# MCU.net
KiCad netlist of a schematic drawn in Altium Designer
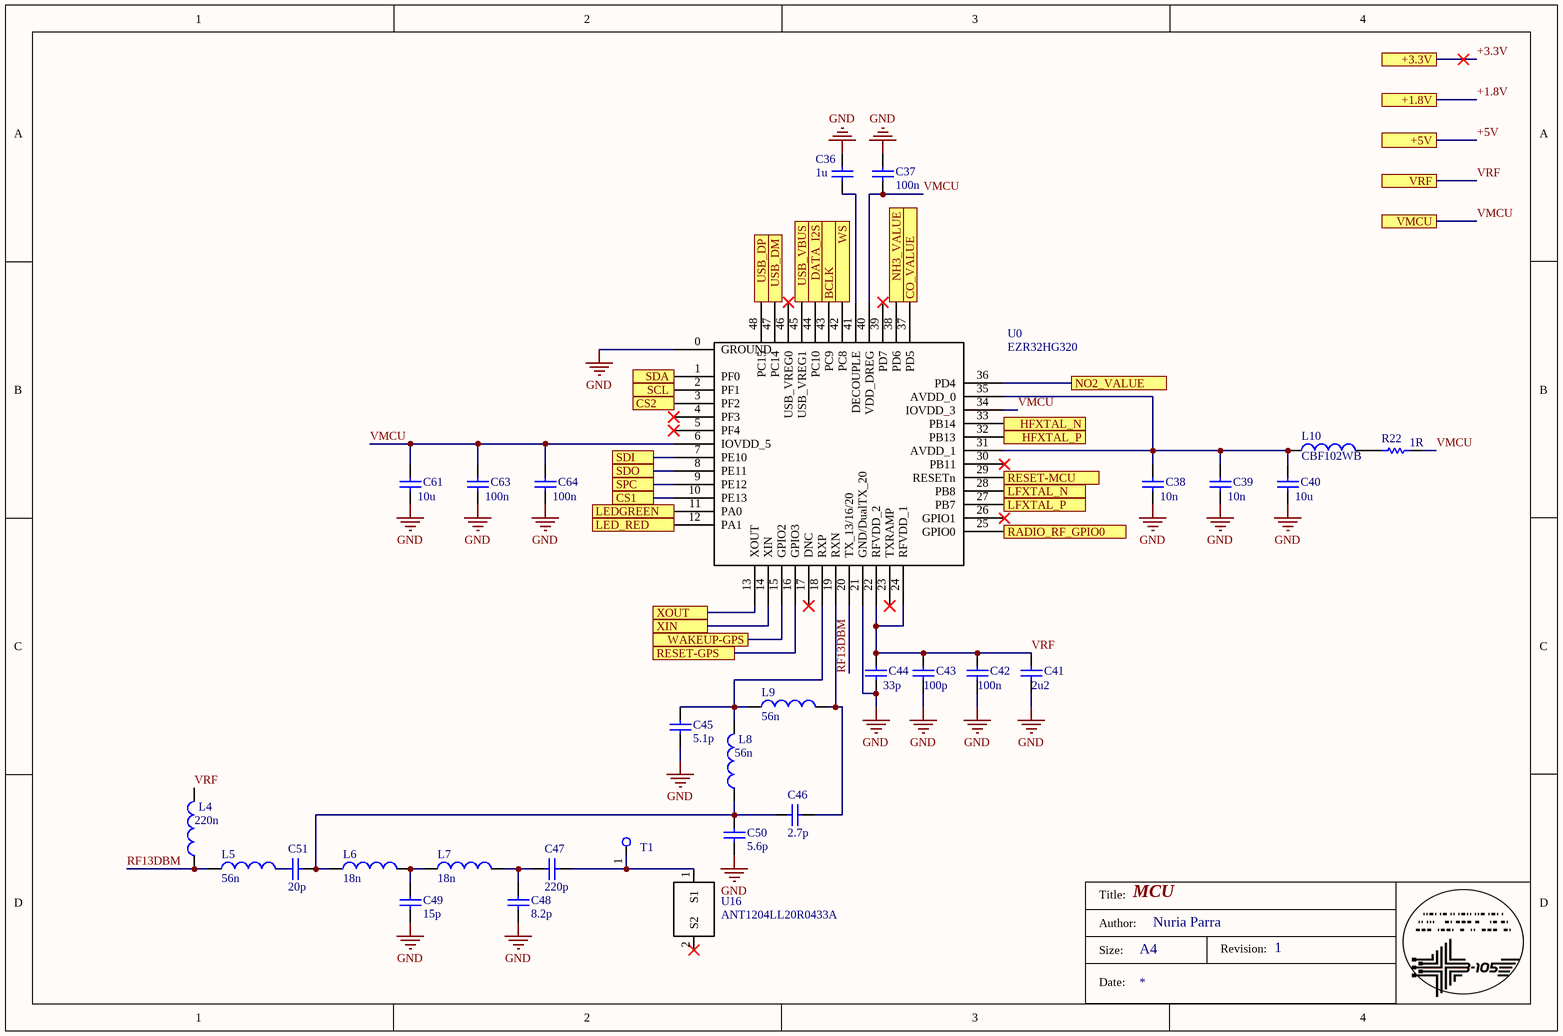
[diagram p0: MCU.SchDoc]

(export (version "E")
  (design (tool "Eeschema 10.0.6"))
  (components
    (comp (ref "C36")
      (value "1u")
      (footprint "0603 Cap")
      (fields (field (name "Comment") "Cap"))
      (libsource (lib "B105rlc") (part "Cap"))
    )
    (comp (ref "C37")
      (value "100n")
      (footprint "0603 Cap")
      (fields (field (name "Comment") "Cap"))
      (libsource (lib "B105rlc") (part "Cap"))
    )
    (comp (ref "C38")
      (value "10n")
      (footprint "0603 Cap")
      (fields (field (name "Comment") "Cap"))
      (libsource (lib "B105rlc") (part "Cap"))
    )
    (comp (ref "C39")
      (value "10n")
      (footprint "0603 Cap")
      (fields (field (name "Comment") "Cap"))
      (libsource (lib "B105rlc") (part "Cap"))
    )
    (comp (ref "C40")
      (value "10u")
      (footprint "0603 Cap")
      (fields (field (name "Comment") "Cap"))
      (libsource (lib "B105rlc") (part "Cap"))
    )
    (comp (ref "C41")
      (value "2u2")
      (footprint "0603 Cap")
      (fields (field (name "Comment") "Cap"))
      (libsource (lib "B105rlc") (part "Cap"))
    )
    (comp (ref "C42")
      (value "100n")
      (footprint "0603 Cap")
      (fields (field (name "Comment") "Cap"))
      (libsource (lib "B105rlc") (part "Cap"))
    )
    (comp (ref "C43")
      (value "100p")
      (footprint "0603 Cap")
      (fields (field (name "Comment") "Cap"))
      (libsource (lib "B105rlc") (part "Cap"))
    )
    (comp (ref "C44")
      (value "33p")
      (footprint "0603 Cap")
      (fields (field (name "Comment") "Cap"))
      (libsource (lib "B105rlc") (part "Cap"))
    )
    (comp (ref "C45")
      (value "5.1p")
      (footprint "0603 Cap")
      (fields (field (name "Comment") "Cap"))
      (libsource (lib "B105rlc") (part "Cap"))
    )
    (comp (ref "C46")
      (value "2.7p")
      (footprint "0603 Cap")
      (fields (field (name "Comment") "Cap"))
      (libsource (lib "B105rlc") (part "Cap"))
    )
    (comp (ref "C47")
      (value "220p")
      (footprint "0603 Cap")
      (fields (field (name "Comment") "Cap"))
      (libsource (lib "B105rlc") (part "Cap"))
    )
    (comp (ref "C48")
      (value "8.2p")
      (footprint "0603 Cap")
      (fields (field (name "Comment") "Cap"))
      (libsource (lib "B105rlc") (part "Cap"))
    )
    (comp (ref "C49")
      (value "15p")
      (footprint "0603 Cap")
      (fields (field (name "Comment") "Cap"))
      (libsource (lib "B105rlc") (part "Cap"))
    )
    (comp (ref "C50")
      (value "5.6p")
      (footprint "0603 Cap")
      (fields (field (name "Comment") "Cap"))
      (libsource (lib "B105rlc") (part "Cap"))
    )
    (comp (ref "C51")
      (value "20p")
      (footprint "0603 Cap")
      (fields (field (name "Comment") "Cap"))
      (libsource (lib "B105rlc") (part "Cap"))
    )
    (comp (ref "C61")
      (value "10u")
      (footprint "0603 Cap")
      (fields (field (name "Comment") "Cap"))
      (libsource (lib "B105rlc") (part "Cap"))
    )
    (comp (ref "C63")
      (value "100n")
      (footprint "0603 Cap")
      (fields (field (name "Comment") "Cap"))
      (libsource (lib "B105rlc") (part "Cap"))
    )
    (comp (ref "C64")
      (value "100n")
      (footprint "0603 Cap")
      (fields (field (name "Comment") "Cap"))
      (libsource (lib "B105rlc") (part "Cap"))
    )
    (comp (ref "L4")
      (value "220n")
      (footprint "0603 IND")
      (fields (field (name "Comment") "L?"))
      (libsource (lib "B105rlc") (part "Ind"))
    )
    (comp (ref "L5")
      (value "56n")
      (footprint "0603 IND")
      (fields (field (name "Comment") "L?"))
      (libsource (lib "B105rlc") (part "Ind"))
    )
    (comp (ref "L6")
      (value "18n")
      (footprint "0603 IND")
      (fields (field (name "Comment") "L?"))
      (libsource (lib "B105rlc") (part "Ind"))
    )
    (comp (ref "L7")
      (value "18n")
      (footprint "0603 IND")
      (fields (field (name "Comment") "L?"))
      (libsource (lib "B105rlc") (part "Ind"))
    )
    (comp (ref "L8")
      (value "56n")
      (footprint "0603 IND")
      (fields (field (name "Comment") "L?"))
      (libsource (lib "B105rlc") (part "Ind"))
    )
    (comp (ref "L9")
      (value "56n")
      (footprint "0603 IND")
      (fields (field (name "Comment") "L?"))
      (libsource (lib "B105rlc") (part "Ind"))
    )
    (comp (ref "L10")
      (value "CBF102WB")
      (footprint "0603 IND")
      (fields (field (name "Comment") "L?"))
      (libsource (lib "B105rlc") (part "Ind"))
    )
    (comp (ref "R22")
      (value "1R")
      (footprint "0603 Res")
      (fields (field (name "Comment") "Res"))
      (libsource (lib "B105rlc") (part "Res"))
    )
    (comp (ref "T1")
      (value "testpoint")
      (footprint "testpoint")
      (libsource (lib "Libreria Nuria") (part "testpoint"))
    )
    (comp (ref "U0")
      (value "EZR32HG320")
      (footprint "EZ32HG")
      (libsource (lib "Libreria Nuria") (part "EZR32HG320"))
    )
    (comp (ref "U16")
      (value "ANT1204LL20R0433A")
      (footprint "ANT1204LL20R0433A")
      (libsource (lib "Libreria Nuria") (part "ANT1204LL20R0433A"))
    )
  )
  (nets
    (net (code "4") (name "/BCLK") (class "Default")
      (node (ref "U0") (pin "43") (pinfunction "PC9_43") (pintype "passive"))
    )
    (net (code "5") (name "/CO_VALUE") (class "Default")
      (node (ref "U0") (pin "37") (pinfunction "PD5_37") (pintype "passive"))
    )
    (net (code "6") (name "/CS1") (class "Default")
      (node (ref "U0") (pin "10") (pinfunction "PE13_10") (pintype "passive"))
    )
    (net (code "7") (name "/CS2") (class "Default")
      (node (ref "U0") (pin "3") (pinfunction "PF2_3") (pintype "passive"))
    )
    (net (code "8") (name "/DATA_I2S") (class "Default")
      (node (ref "U0") (pin "44") (pinfunction "PC10_44") (pintype "passive"))
    )
    (net (code "9") (name "/HFXTAL_N") (class "Default")
      (node (ref "U0") (pin "33") (pinfunction "PB14_33") (pintype "passive"))
    )
    (net (code "10") (name "/HFXTAL_P") (class "Default")
      (node (ref "U0") (pin "32") (pinfunction "PB13_32") (pintype "passive"))
    )
    (net (code "11") (name "/LEDGREEN") (class "Default")
      (node (ref "U0") (pin "11") (pinfunction "PA0_11") (pintype "passive"))
    )
    (net (code "12") (name "/LED_RED") (class "Default")
      (node (ref "U0") (pin "12") (pinfunction "PA1_12") (pintype "passive"))
    )
    (net (code "13") (name "/LFXTAL_N") (class "Default")
      (node (ref "U0") (pin "28") (pinfunction "PB8_28") (pintype "passive"))
    )
    (net (code "14") (name "/LFXTAL_P") (class "Default")
      (node (ref "U0") (pin "27") (pinfunction "PB7_27") (pintype "passive"))
    )
    (net (code "15") (name "/NH3_VALUE") (class "Default")
      (node (ref "U0") (pin "38") (pinfunction "PD6_38") (pintype "passive"))
    )
    (net (code "16") (name "/NO2_VALUE") (class "Default")
      (node (ref "U0") (pin "36") (pinfunction "PD4_36") (pintype "passive"))
    )
    (net (code "17") (name "/RADIO_RF_GPIO0") (class "Default")
      (node (ref "U0") (pin "25") (pinfunction "GPIO0_25") (pintype "passive"))
    )
    (net (code "18") (name "/RESET-GPS") (class "Default")
      (node (ref "U0") (pin "16") (pinfunction "GPIO3_16") (pintype "passive"))
    )
    (net (code "19") (name "/RESET-MCU") (class "Default")
      (node (ref "U0") (pin "29") (pinfunction "RESETn_29") (pintype "passive"))
    )
    (net (code "20") (name "/RF13DBM") (class "Default")
      (node (ref "L4") (pin "1") (pinfunction "1_1") (pintype "passive"))
      (node (ref "L5") (pin "1") (pinfunction "1_1") (pintype "passive"))
      (node (ref "U0") (pin "20") (pinfunction "TX_13/16/20_20") (pintype "passive"))
    )
    (net (code "21") (name "/SCL") (class "Default")
      (node (ref "U0") (pin "2") (pinfunction "PF1_2") (pintype "passive"))
    )
    (net (code "22") (name "/SDA") (class "Default")
      (node (ref "U0") (pin "1") (pinfunction "PF0_1") (pintype "passive"))
    )
    (net (code "23") (name "/SDI") (class "Default")
      (node (ref "U0") (pin "7") (pinfunction "PE10_7") (pintype "passive"))
    )
    (net (code "24") (name "/SDO") (class "Default")
      (node (ref "U0") (pin "8") (pinfunction "PE11_8") (pintype "passive"))
    )
    (net (code "25") (name "/SPC") (class "Default")
      (node (ref "U0") (pin "9") (pinfunction "PE12_9") (pintype "passive"))
    )
    (net (code "26") (name "/USB_DM") (class "Default")
      (node (ref "U0") (pin "47") (pinfunction "PC14_47") (pintype "passive"))
    )
    (net (code "27") (name "/USB_DP") (class "Default")
      (node (ref "U0") (pin "48") (pinfunction "PC15_48") (pintype "passive"))
    )
    (net (code "28") (name "/USB_VBUS") (class "Default")
      (node (ref "U0") (pin "45") (pinfunction "USB_VREG1_45") (pintype "passive"))
    )
    (net (code "29") (name "/VMCU") (class "Default")
      (node (ref "C37") (pin "2") (pinfunction "2_2") (pintype "passive"))
      (node (ref "C61") (pin "2") (pinfunction "2_2") (pintype "passive"))
      (node (ref "C63") (pin "2") (pinfunction "2_2") (pintype "passive"))
      (node (ref "C64") (pin "2") (pinfunction "2_2") (pintype "passive"))
      (node (ref "R22") (pin "2") (pinfunction "2_2") (pintype "passive"))
      (node (ref "U0") (pin "34") (pinfunction "IOVDD_3_34") (pintype "power_in"))
      (node (ref "U0") (pin "40") (pinfunction "VDD_DREG_40") (pintype "power_in"))
      (node (ref "U0") (pin "6") (pinfunction "IOVDD_5_6") (pintype "power_in"))
    )
    (net (code "30") (name "/VRF") (class "Default")
      (node (ref "C41") (pin "2") (pinfunction "2_2") (pintype "passive"))
      (node (ref "C42") (pin "2") (pinfunction "2_2") (pintype "passive"))
      (node (ref "C43") (pin "2") (pinfunction "2_2") (pintype "passive"))
      (node (ref "C44") (pin "2") (pinfunction "2_2") (pintype "passive"))
      (node (ref "L4") (pin "2") (pinfunction "2_2") (pintype "passive"))
      (node (ref "U0") (pin "22") (pinfunction "RFVDD_2_22") (pintype "power_in"))
      (node (ref "U0") (pin "24") (pinfunction "RFVDD_1_24") (pintype "power_in"))
    )
    (net (code "31") (name "/WAKEUP-GPS") (class "Default")
      (node (ref "U0") (pin "15") (pinfunction "GPIO2_15") (pintype "passive"))
    )
    (net (code "32") (name "/WS") (class "Default")
      (node (ref "U0") (pin "42") (pinfunction "PC8_42") (pintype "passive"))
    )
    (net (code "33") (name "/XIN") (class "Default")
      (node (ref "U0") (pin "14") (pinfunction "XIN_14") (pintype "passive"))
    )
    (net (code "34") (name "/XOUT") (class "Default")
      (node (ref "U0") (pin "13") (pinfunction "XOUT_13") (pintype "passive"))
    )
    (net (code "35") (name "GND") (class "Default")
      (node (ref "C36") (pin "1") (pinfunction "1_1") (pintype "passive"))
      (node (ref "C37") (pin "1") (pinfunction "1_1") (pintype "passive"))
      (node (ref "C38") (pin "1") (pinfunction "1_1") (pintype "passive"))
      (node (ref "C39") (pin "1") (pinfunction "1_1") (pintype "passive"))
      (node (ref "C40") (pin "1") (pinfunction "1_1") (pintype "passive"))
      (node (ref "C41") (pin "1") (pinfunction "1_1") (pintype "passive"))
      (node (ref "C42") (pin "1") (pinfunction "1_1") (pintype "passive"))
      (node (ref "C43") (pin "1") (pinfunction "1_1") (pintype "passive"))
      (node (ref "C44") (pin "1") (pinfunction "1_1") (pintype "passive"))
      (node (ref "C45") (pin "2") (pinfunction "2_2") (pintype "passive"))
      (node (ref "C48") (pin "2") (pinfunction "2_2") (pintype "passive"))
      (node (ref "C49") (pin "2") (pinfunction "2_2") (pintype "passive"))
      (node (ref "C50") (pin "2") (pinfunction "2_2") (pintype "passive"))
      (node (ref "C61") (pin "1") (pinfunction "1_1") (pintype "passive"))
      (node (ref "C63") (pin "1") (pinfunction "1_1") (pintype "passive"))
      (node (ref "C64") (pin "1") (pinfunction "1_1") (pintype "passive"))
      (node (ref "U0") (pin "0") (pinfunction "GROUND_0") (pintype "power_in"))
      (node (ref "U0") (pin "21") (pinfunction "GND/DualTX_20_21") (pintype "passive"))
    )
    (net (code "36") (name "Net-(C46-Pad2)") (class "Default")
      (node (ref "C46") (pin "2") (pinfunction "2_2") (pintype "passive"))
      (node (ref "C50") (pin "1") (pinfunction "1_1") (pintype "passive"))
      (node (ref "C51") (pin "1") (pinfunction "1_1") (pintype "passive"))
      (node (ref "L6") (pin "1") (pinfunction "1_1") (pintype "passive"))
      (node (ref "L8") (pin "1") (pinfunction "1_1") (pintype "passive"))
    )
    (net (code "37") (name "Net-(C47-Pad2)") (class "Default")
      (node (ref "C47") (pin "2") (pinfunction "2_2") (pintype "passive"))
      (node (ref "C48") (pin "1") (pinfunction "1_1") (pintype "passive"))
      (node (ref "L7") (pin "2") (pinfunction "2_2") (pintype "passive"))
    )
    (net (code "38") (name "Net-(C49-Pad1)") (class "Default")
      (node (ref "C49") (pin "1") (pinfunction "1_1") (pintype "passive"))
      (node (ref "L6") (pin "2") (pinfunction "2_2") (pintype "passive"))
      (node (ref "L7") (pin "1") (pinfunction "1_1") (pintype "passive"))
    )
    (net (code "39") (name "Net-(C51-Pad2)") (class "Default")
      (node (ref "C51") (pin "2") (pinfunction "2_2") (pintype "passive"))
      (node (ref "L5") (pin "2") (pinfunction "2_2") (pintype "passive"))
    )
    (net (code "40") (name "Net-(L10-Pad2)") (class "Default")
      (node (ref "L10") (pin "2") (pinfunction "2_2") (pintype "passive"))
      (node (ref "R22") (pin "1") (pinfunction "1_1") (pintype "passive"))
    )
    (net (code "41") (name "Net-(T1-TP)") (class "Default")
      (node (ref "C47") (pin "1") (pinfunction "1_1") (pintype "passive"))
      (node (ref "T1") (pin "1") (pinfunction "TP_1") (pintype "passive"))
      (node (ref "U16") (pin "1") (pinfunction "S1_1") (pintype "power_in"))
    )
    (net (code "42") (name "Net-(U0-AVDD_0)") (class "Default")
      (node (ref "C38") (pin "2") (pinfunction "2_2") (pintype "passive"))
      (node (ref "C39") (pin "2") (pinfunction "2_2") (pintype "passive"))
      (node (ref "C40") (pin "2") (pinfunction "2_2") (pintype "passive"))
      (node (ref "L10") (pin "1") (pinfunction "1_1") (pintype "passive"))
      (node (ref "U0") (pin "31") (pinfunction "AVDD_1_31") (pintype "power_in"))
      (node (ref "U0") (pin "35") (pinfunction "AVDD_0_35") (pintype "power_in"))
    )
    (net (code "43") (name "Net-(U0-DECOUPLE)") (class "Default")
      (node (ref "C36") (pin "2") (pinfunction "2_2") (pintype "passive"))
      (node (ref "U0") (pin "41") (pinfunction "DECOUPLE_41") (pintype "passive"))
    )
    (net (code "44") (name "Net-(U0-RXN)") (class "Default")
      (node (ref "C46") (pin "1") (pinfunction "1_1") (pintype "passive"))
      (node (ref "L9") (pin "2") (pinfunction "2_2") (pintype "passive"))
      (node (ref "U0") (pin "19") (pinfunction "RXN_19") (pintype "passive"))
    )
    (net (code "45") (name "Net-(U0-RXP)") (class "Default")
      (node (ref "C45") (pin "1") (pinfunction "1_1") (pintype "passive"))
      (node (ref "L8") (pin "2") (pinfunction "2_2") (pintype "passive"))
      (node (ref "L9") (pin "1") (pinfunction "1_1") (pintype "passive"))
      (node (ref "U0") (pin "18") (pinfunction "RXP_18") (pintype "passive"))
    )
    (net (code "46") (name "unconnected-(U0-DNC-Pad17)") (class "Default")
      (node (ref "U0") (pin "17") (pinfunction "DNC_17") (pintype "passive+no_connect"))
    )
    (net (code "47") (name "unconnected-(U0-GPIO1-Pad26)") (class "Default")
      (node (ref "U0") (pin "26") (pinfunction "GPIO1_26") (pintype "passive+no_connect"))
    )
    (net (code "48") (name "unconnected-(U0-PB11-Pad30)") (class "Default")
      (node (ref "U0") (pin "30") (pinfunction "PB11_30") (pintype "passive+no_connect"))
    )
    (net (code "49") (name "unconnected-(U0-PD7-Pad39)") (class "Default")
      (node (ref "U0") (pin "39") (pinfunction "PD7_39") (pintype "passive+no_connect"))
    )
    (net (code "50") (name "unconnected-(U0-PF3-Pad4)") (class "Default")
      (node (ref "U0") (pin "4") (pinfunction "PF3_4") (pintype "passive+no_connect"))
    )
    (net (code "51") (name "unconnected-(U0-PF4-Pad5)") (class "Default")
      (node (ref "U0") (pin "5") (pinfunction "PF4_5") (pintype "passive+no_connect"))
    )
    (net (code "52") (name "unconnected-(U0-TXRAMP-Pad23)") (class "Default")
      (node (ref "U0") (pin "23") (pinfunction "TXRAMP_23") (pintype "passive+no_connect"))
    )
    (net (code "53") (name "unconnected-(U0-USB_VREG0-Pad46)") (class "Default")
      (node (ref "U0") (pin "46") (pinfunction "USB_VREG0_46") (pintype "passive+no_connect"))
    )
    (net (code "54") (name "unconnected-(U16-S2-Pad2)") (class "Default")
      (node (ref "U16") (pin "2") (pinfunction "S2_2") (pintype "passive+no_connect"))
    )
  )
)
